# CAN.net
KiCad netlist of a schematic drawn in Altium Designer
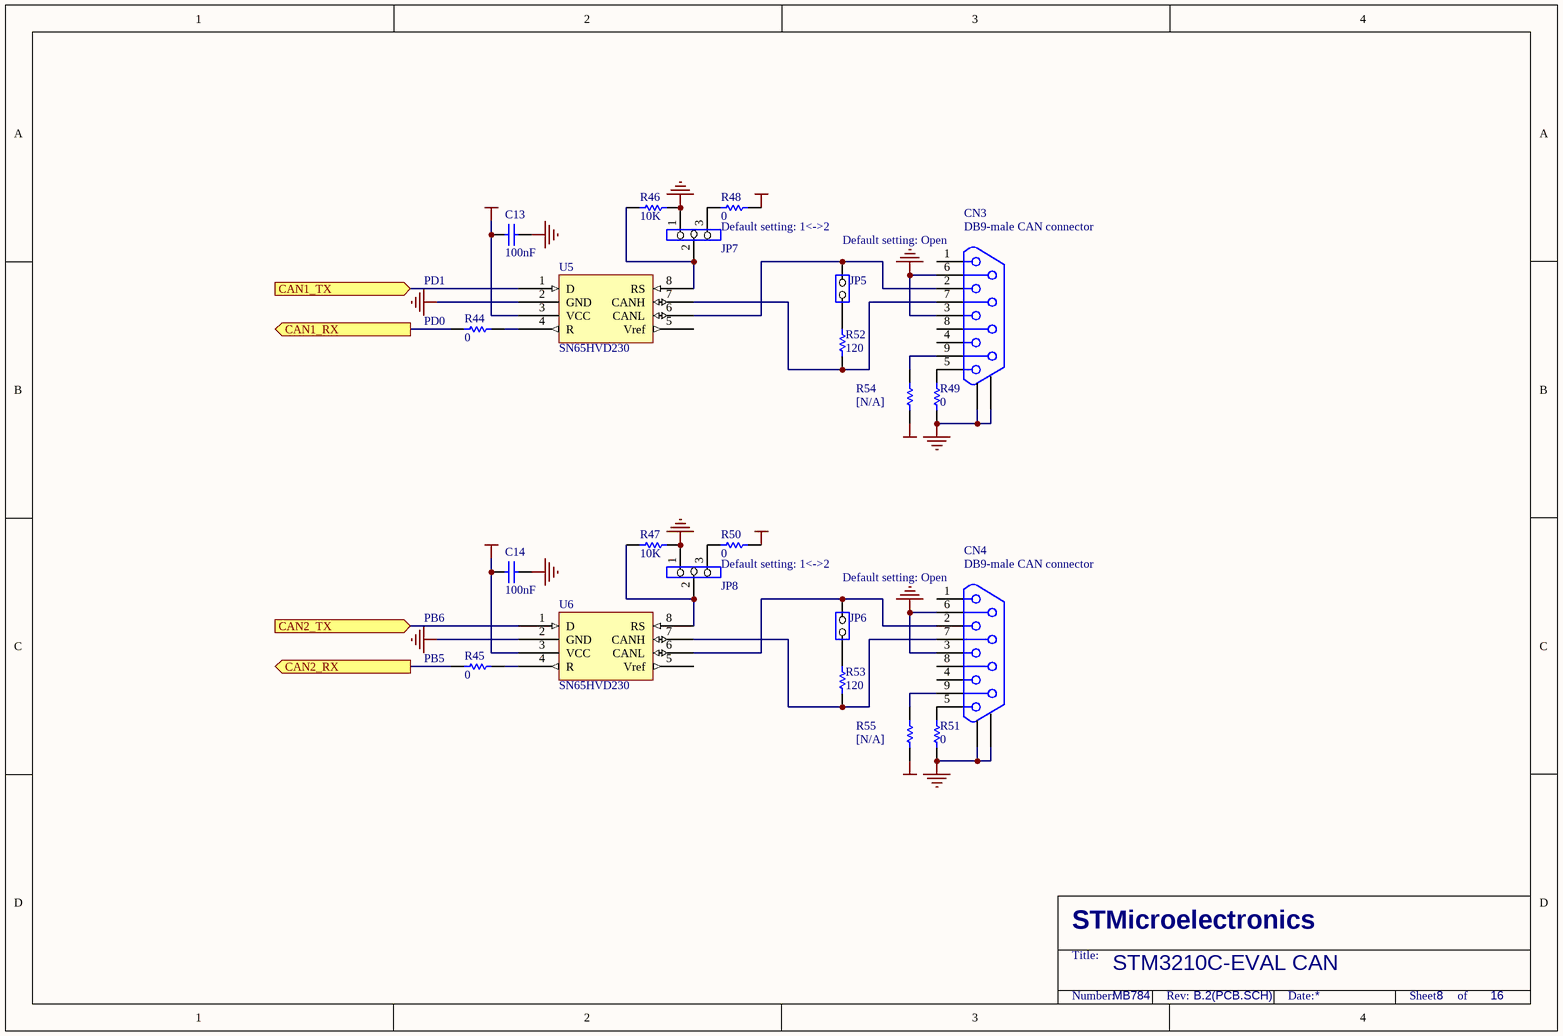
[diagram p0: CAN.SchDoc]

(export (version "E")
  (design (tool "Eeschema 10.0.6"))
  (components
    (comp (ref "C13")
      (value "100nF")
      (footprint "0603C")
      (description "Capacitor")
      (fields (field (name "PUBLISHER") "Altium Limited"))
      (libsource (lib "Miscellaneous Devices") (part "CAP"))
    )
    (comp (ref "C14")
      (value "100nF")
      (footprint "0603C")
      (description "Capacitor")
      (fields (field (name "PUBLISHER") "Altium Limited"))
      (libsource (lib "Miscellaneous Devices") (part "CAP"))
    )
    (comp (ref "CN3") (value "DB9-male CAN connector") (footprint "DB9/M") (libsource (lib "*") (part "DB9")))
    (comp (ref "CN4") (value "DB9-male CAN connector") (footprint "DB9/M") (libsource (lib "*") (part "DB9")))
    (comp (ref "JP5") (value "~") (footprint "SIP2") (libsource (lib "*") (part "JP2")))
    (comp (ref "JP6") (value "~") (footprint "SIP2") (libsource (lib "*") (part "JP2")))
    (comp (ref "JP7") (value "~") (footprint "SIP3") (libsource (lib "STR910_SCHLIB") (part "Jumper3")))
    (comp (ref "JP8") (value "~") (footprint "SIP3") (libsource (lib "STR910_SCHLIB") (part "Jumper3")))
    (comp (ref "R44")
      (value "0")
      (footprint "0603R")
      (description "Resistor")
      (fields (field (name "PUBLISHER") "Altium Limited"))
      (libsource (lib "Miscellaneous Devices") (part "Res1"))
    )
    (comp (ref "R45")
      (value "0")
      (footprint "0603R")
      (description "Resistor")
      (fields (field (name "PUBLISHER") "Altium Limited"))
      (libsource (lib "Miscellaneous Devices") (part "Res1"))
    )
    (comp (ref "R46")
      (value "10K")
      (footprint "0603R")
      (description "Resistor")
      (fields (field (name "PUBLISHER") "Altium Limited"))
      (libsource (lib "Miscellaneous Devices") (part "res1"))
    )
    (comp (ref "R47")
      (value "10K")
      (footprint "0603R")
      (description "Resistor")
      (fields (field (name "PUBLISHER") "Altium Limited"))
      (libsource (lib "Miscellaneous Devices") (part "res1"))
    )
    (comp (ref "R48")
      (value "0")
      (footprint "0603R")
      (description "Resistor")
      (fields (field (name "PUBLISHER") "Altium Limited"))
      (libsource (lib "Miscellaneous Devices") (part "res1"))
    )
    (comp (ref "R49")
      (value "0")
      (footprint "0603R")
      (description "Resistor")
      (fields (field (name "PUBLISHER") "Altium Limited"))
      (libsource (lib "Miscellaneous Devices") (part "res1"))
    )
    (comp (ref "R50")
      (value "0")
      (footprint "0603R")
      (description "Resistor")
      (fields (field (name "PUBLISHER") "Altium Limited"))
      (libsource (lib "Miscellaneous Devices") (part "res1"))
    )
    (comp (ref "R51")
      (value "0")
      (footprint "0603R")
      (description "Resistor")
      (fields (field (name "PUBLISHER") "Altium Limited"))
      (libsource (lib "Miscellaneous Devices") (part "res1"))
    )
    (comp (ref "R52")
      (value "120")
      (footprint "0603R")
      (description "Resistor")
      (fields (field (name "PUBLISHER") "Altium Limited"))
      (libsource (lib "Miscellaneous Devices") (part "res1"))
    )
    (comp (ref "R53")
      (value "120")
      (footprint "0603R")
      (description "Resistor")
      (fields (field (name "PUBLISHER") "Altium Limited"))
      (libsource (lib "Miscellaneous Devices") (part "res1"))
    )
    (comp (ref "R54")
      (value "[N/A]")
      (footprint "0603R")
      (description "Resistor")
      (fields (field (name "PUBLISHER") "Altium Limited"))
      (libsource (lib "Miscellaneous Devices") (part "res1"))
    )
    (comp (ref "R55")
      (value "[N/A]")
      (footprint "0603R")
      (description "Resistor")
      (fields (field (name "PUBLISHER") "Altium Limited"))
      (libsource (lib "Miscellaneous Devices") (part "res1"))
    )
    (comp (ref "U5")
      (value "SN65HVD230")
      (footprint "SO8")
      (libsource (lib "STR910_SCHLIB") (part "SN65HVD230D"))
    )
    (comp (ref "U6")
      (value "SN65HVD230")
      (footprint "SO8")
      (libsource (lib "STR910_SCHLIB") (part "SN65HVD230D"))
    )
  )
  (nets
    (net (code "1") (name "+3V3") (class "Default")
      (node (ref "C13") (pin "2") (pinfunction "2_2") (pintype "passive"))
      (node (ref "C14") (pin "2") (pinfunction "2_2") (pintype "passive"))
      (node (ref "R48") (pin "2") (pinfunction "2_2") (pintype "passive"))
      (node (ref "R50") (pin "2") (pinfunction "2_2") (pintype "passive"))
      (node (ref "R54") (pin "1") (pinfunction "1_1") (pintype "passive"))
      (node (ref "R55") (pin "1") (pinfunction "1_1") (pintype "passive"))
      (node (ref "U5") (pin "3") (pinfunction "VCC_3") (pintype "power_in"))
      (node (ref "U6") (pin "3") (pinfunction "VCC_3") (pintype "power_in"))
    )
    (net (code "2") (name "/CAN1_RX") (class "Default")
      (node (ref "R44") (pin "2") (pinfunction "2_2") (pintype "passive"))
    )
    (net (code "3") (name "/CAN1_TX") (class "Default")
      (node (ref "U5") (pin "1") (pinfunction "D_1") (pintype "input"))
    )
    (net (code "4") (name "/CAN2_RX") (class "Default")
      (node (ref "R45") (pin "2") (pinfunction "2_2") (pintype "passive"))
    )
    (net (code "5") (name "/CAN2_TX") (class "Default")
      (node (ref "U6") (pin "1") (pinfunction "D_1") (pintype "input"))
    )
    (net (code "6") (name "GND") (class "Default")
      (node (ref "C13") (pin "1") (pinfunction "1_1") (pintype "passive"))
      (node (ref "C14") (pin "1") (pinfunction "1_1") (pintype "passive"))
      (node (ref "CN3") (pin "0") (pinfunction "0_0") (pintype "passive"))
      (node (ref "CN3") (pin "3") (pinfunction "3_3") (pintype "passive"))
      (node (ref "CN3") (pin "6") (pinfunction "6_6") (pintype "passive"))
      (node (ref "CN4") (pin "0") (pinfunction "0_0") (pintype "passive"))
      (node (ref "CN4") (pin "3") (pinfunction "3_3") (pintype "passive"))
      (node (ref "CN4") (pin "6") (pinfunction "6_6") (pintype "passive"))
      (node (ref "JP7") (pin "1") (pintype "passive"))
      (node (ref "JP8") (pin "1") (pintype "passive"))
      (node (ref "R46") (pin "2") (pinfunction "2_2") (pintype "passive"))
      (node (ref "R47") (pin "2") (pinfunction "2_2") (pintype "passive"))
      (node (ref "R49") (pin "1") (pinfunction "1_1") (pintype "passive"))
      (node (ref "R51") (pin "1") (pinfunction "1_1") (pintype "passive"))
      (node (ref "U5") (pin "2") (pinfunction "GND_2") (pintype "power_in"))
      (node (ref "U6") (pin "2") (pinfunction "GND_2") (pintype "power_in"))
    )
    (net (code "7") (name "Net-(CN3-Pad5)") (class "Default")
      (node (ref "CN3") (pin "5") (pinfunction "5_5") (pintype "passive"))
      (node (ref "R49") (pin "2") (pinfunction "2_2") (pintype "passive"))
    )
    (net (code "8") (name "Net-(CN3-Pad9)") (class "Default")
      (node (ref "CN3") (pin "9") (pinfunction "9_9") (pintype "passive"))
      (node (ref "R54") (pin "2") (pinfunction "2_2") (pintype "passive"))
    )
    (net (code "9") (name "Net-(CN4-Pad5)") (class "Default")
      (node (ref "CN4") (pin "5") (pinfunction "5_5") (pintype "passive"))
      (node (ref "R51") (pin "2") (pinfunction "2_2") (pintype "passive"))
    )
    (net (code "10") (name "Net-(CN4-Pad9)") (class "Default")
      (node (ref "CN4") (pin "9") (pinfunction "9_9") (pintype "passive"))
      (node (ref "R55") (pin "2") (pinfunction "2_2") (pintype "passive"))
    )
    (net (code "11") (name "Net-(JP5-COMMON)") (class "Default")
      (node (ref "JP5") (pin "1") (pinfunction "COMMON_1") (pintype "passive"))
      (node (ref "R52") (pin "2") (pinfunction "2_2") (pintype "passive"))
    )
    (net (code "12") (name "Net-(JP5-NO)") (class "Default")
      (node (ref "CN3") (pin "2") (pinfunction "2_2") (pintype "passive"))
      (node (ref "JP5") (pin "2") (pinfunction "NO_2") (pintype "passive"))
      (node (ref "U5") (pin "6") (pinfunction "CANL_6") (pintype "bidirectional"))
    )
    (net (code "13") (name "Net-(JP6-COMMON)") (class "Default")
      (node (ref "JP6") (pin "1") (pinfunction "COMMON_1") (pintype "passive"))
      (node (ref "R53") (pin "2") (pinfunction "2_2") (pintype "passive"))
    )
    (net (code "14") (name "Net-(JP6-NO)") (class "Default")
      (node (ref "CN4") (pin "2") (pinfunction "2_2") (pintype "passive"))
      (node (ref "JP6") (pin "2") (pinfunction "NO_2") (pintype "passive"))
      (node (ref "U6") (pin "6") (pinfunction "CANL_6") (pintype "bidirectional"))
    )
    (net (code "15") (name "Net-(JP7-Pad3)") (class "Default")
      (node (ref "JP7") (pin "3") (pintype "passive"))
      (node (ref "R48") (pin "1") (pinfunction "1_1") (pintype "passive"))
    )
    (net (code "16") (name "Net-(JP8-Pad3)") (class "Default")
      (node (ref "JP8") (pin "3") (pintype "passive"))
      (node (ref "R50") (pin "1") (pinfunction "1_1") (pintype "passive"))
    )
    (net (code "17") (name "Net-(U5-CANH)") (class "Default")
      (node (ref "CN3") (pin "7") (pinfunction "7_7") (pintype "passive"))
      (node (ref "R52") (pin "1") (pinfunction "1_1") (pintype "passive"))
      (node (ref "U5") (pin "7") (pinfunction "CANH_7") (pintype "bidirectional"))
    )
    (net (code "18") (name "Net-(U5-R)") (class "Default")
      (node (ref "R44") (pin "1") (pinfunction "1_1") (pintype "passive"))
      (node (ref "U5") (pin "4") (pinfunction "R_4") (pintype "output"))
    )
    (net (code "19") (name "Net-(U5-RS)") (class "Default")
      (node (ref "JP7") (pin "2") (pintype "passive"))
      (node (ref "R46") (pin "1") (pinfunction "1_1") (pintype "passive"))
      (node (ref "U5") (pin "8") (pinfunction "RS_8") (pintype "input"))
    )
    (net (code "20") (name "Net-(U6-CANH)") (class "Default")
      (node (ref "CN4") (pin "7") (pinfunction "7_7") (pintype "passive"))
      (node (ref "R53") (pin "1") (pinfunction "1_1") (pintype "passive"))
      (node (ref "U6") (pin "7") (pinfunction "CANH_7") (pintype "bidirectional"))
    )
    (net (code "21") (name "Net-(U6-R)") (class "Default")
      (node (ref "R45") (pin "1") (pinfunction "1_1") (pintype "passive"))
      (node (ref "U6") (pin "4") (pinfunction "R_4") (pintype "output"))
    )
    (net (code "22") (name "Net-(U6-RS)") (class "Default")
      (node (ref "JP8") (pin "2") (pintype "passive"))
      (node (ref "R47") (pin "1") (pinfunction "1_1") (pintype "passive"))
      (node (ref "U6") (pin "8") (pinfunction "RS_8") (pintype "input"))
    )
    (net (code "23") (name "unconnected-(CN3-Pad1)") (class "Default")
      (node (ref "CN3") (pin "1") (pinfunction "1_1") (pintype "passive"))
    )
    (net (code "24") (name "unconnected-(CN3-Pad4)") (class "Default")
      (node (ref "CN3") (pin "4") (pinfunction "4_4") (pintype "passive"))
    )
    (net (code "25") (name "unconnected-(CN3-Pad8)") (class "Default")
      (node (ref "CN3") (pin "8") (pinfunction "8_8") (pintype "passive"))
    )
    (net (code "26") (name "unconnected-(CN4-Pad1)") (class "Default")
      (node (ref "CN4") (pin "1") (pinfunction "1_1") (pintype "passive"))
    )
    (net (code "27") (name "unconnected-(CN4-Pad4)") (class "Default")
      (node (ref "CN4") (pin "4") (pinfunction "4_4") (pintype "passive"))
    )
    (net (code "28") (name "unconnected-(CN4-Pad8)") (class "Default")
      (node (ref "CN4") (pin "8") (pinfunction "8_8") (pintype "passive"))
    )
    (net (code "29") (name "unconnected-(U5-Vref-Pad5)") (class "Default")
      (node (ref "U5") (pin "5") (pinfunction "Vref_5") (pintype "output"))
    )
    (net (code "30") (name "unconnected-(U6-Vref-Pad5)") (class "Default")
      (node (ref "U6") (pin "5") (pinfunction "Vref_5") (pintype "output"))
    )
  )
)
